# Mega_Shield-v13.net
KiCad netlist of a schematic drawn in EAGLE
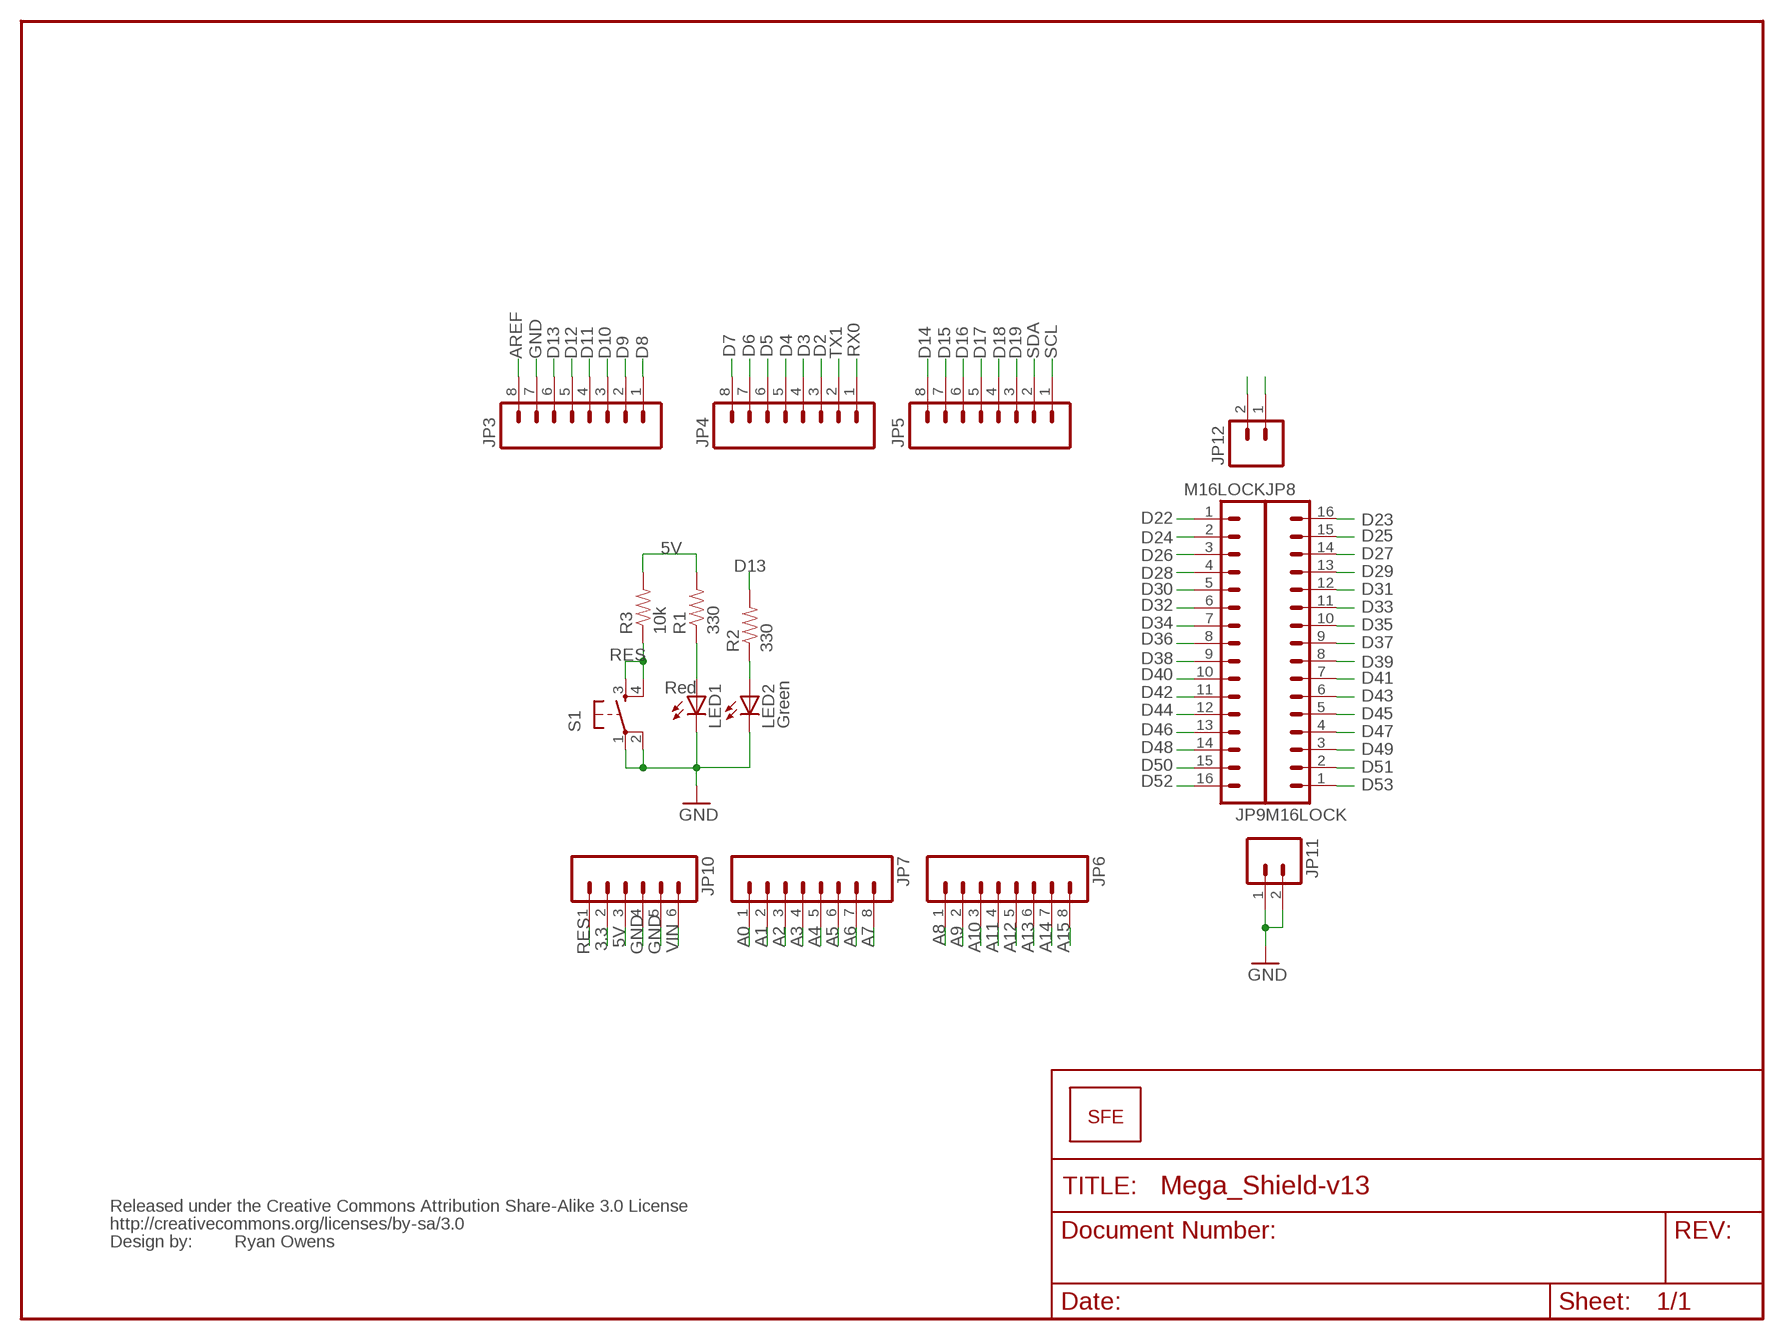
[diagram p0: schematic, sheet 1]

(export (version "E")
  (design (tool "Eeschema 10.0.6"))
  (components
    (comp (ref "JP3")
      (value "M08LOCK")
      (footprint "eagle-import:1X08_LOCK")
      (libsource (lib "eagle-import") (part "M08LOCK"))
    )
    (comp (ref "JP4")
      (value "M08LOCK")
      (footprint "eagle-import:1X08_LOCK")
      (libsource (lib "eagle-import") (part "M08LOCK"))
    )
    (comp (ref "JP5")
      (value "M08LOCK")
      (footprint "eagle-import:1X08_LOCK")
      (libsource (lib "eagle-import") (part "M08LOCK"))
    )
    (comp (ref "JP6")
      (value "M08LOCK")
      (footprint "eagle-import:1X08_LOCK")
      (libsource (lib "eagle-import") (part "M08LOCK"))
    )
    (comp (ref "JP7")
      (value "M08LOCK")
      (footprint "eagle-import:1X08_LOCK")
      (libsource (lib "eagle-import") (part "M08LOCK"))
    )
    (comp (ref "JP8")
      (value "M16LOCK")
      (footprint "eagle-import:1X16_LOCK")
      (libsource (lib "eagle-import") (part "M16LOCK"))
    )
    (comp (ref "JP9")
      (value "M16LOCK")
      (footprint "eagle-import:1X16_LOCK")
      (libsource (lib "eagle-import") (part "M16LOCK"))
    )
    (comp (ref "JP10")
      (value "M06LOCK")
      (footprint "eagle-import:1X06_LOCK")
      (libsource (lib "eagle-import") (part "M06LOCK"))
    )
    (comp (ref "JP11")
      (value "M02LOCK")
      (footprint "eagle-import:1X02_LOCK")
      (libsource (lib "eagle-import") (part "M02LOCK"))
    )
    (comp (ref "JP12")
      (value "M02LOCK")
      (footprint "eagle-import:1X02_LOCK")
      (libsource (lib "eagle-import") (part "M02LOCK"))
    )
    (comp (ref "LED1")
      (value "Red")
      (footprint "eagle-import:LED5MM")
      (libsource (lib "eagle-import") (part "LED5MM"))
    )
    (comp (ref "LED2")
      (value "Green")
      (footprint "eagle-import:LED5MM")
      (libsource (lib "eagle-import") (part "LED5MM"))
    )
    (comp (ref "R1")
      (value "330")
      (footprint "eagle-import:AXIAL-0.3")
      (libsource (lib "eagle-import") (part "RESISTORPTH1"))
    )
    (comp (ref "R2")
      (value "330")
      (footprint "eagle-import:AXIAL-0.3")
      (libsource (lib "eagle-import") (part "RESISTORPTH1"))
    )
    (comp (ref "R3")
      (value "10k")
      (footprint "eagle-import:AXIAL-0.3")
      (libsource (lib "eagle-import") (part "RESISTORPTH1"))
    )
    (comp (ref "S1")
      (value "TAC_SWITCHPTH")
      (footprint "eagle-import:TACTILE-PTH")
      (libsource (lib "eagle-import") (part "TAC_SWITCHPTH"))
    )
    (comp (ref "U$1")
      (value "LOGO-SFENEW")
      (footprint "eagle-import:SFE-NEW-WEBLOGO")
      (libsource (lib "eagle-import") (part "LOGO-SFENEW"))
    )
    (comp (ref "U$2")
      (value "CREATIVE_COMMONS")
      (footprint "eagle-import:CREATIVE_COMMONS")
      (libsource (lib "eagle-import") (part "CREATIVE_COMMONS"))
    )
  )
  (nets
    (net (code "1") (name "/3.3") (class "Default")
      (node (ref "JP10") (pin "2") (pinfunction "2_2") (pintype "passive"))
    )
    (net (code "2") (name "/5V") (class "Default")
      (node (ref "JP10") (pin "3") (pinfunction "3_3") (pintype "passive"))
      (node (ref "R1") (pin "P$2") (pinfunction "2_P$2") (pintype "passive"))
      (node (ref "R3") (pin "P$2") (pinfunction "2_P$2") (pintype "passive"))
    )
    (net (code "3") (name "/5V@1") (class "Default")
      (node (ref "JP12") (pin "1") (pinfunction "1_1") (pintype "passive"))
      (node (ref "JP12") (pin "2") (pinfunction "2_2") (pintype "passive"))
    )
    (net (code "4") (name "/A0") (class "Default")
      (node (ref "JP7") (pin "1") (pinfunction "1_1") (pintype "passive"))
    )
    (net (code "5") (name "/A1") (class "Default")
      (node (ref "JP7") (pin "2") (pinfunction "2_2") (pintype "passive"))
    )
    (net (code "6") (name "/A2") (class "Default")
      (node (ref "JP7") (pin "3") (pinfunction "3_3") (pintype "passive"))
    )
    (net (code "7") (name "/A3") (class "Default")
      (node (ref "JP7") (pin "4") (pinfunction "4_4") (pintype "passive"))
    )
    (net (code "8") (name "/A4") (class "Default")
      (node (ref "JP7") (pin "5") (pinfunction "5_5") (pintype "passive"))
    )
    (net (code "9") (name "/A5") (class "Default")
      (node (ref "JP7") (pin "6") (pinfunction "6_6") (pintype "passive"))
    )
    (net (code "10") (name "/A6") (class "Default")
      (node (ref "JP7") (pin "7") (pinfunction "7_7") (pintype "passive"))
    )
    (net (code "11") (name "/A7") (class "Default")
      (node (ref "JP7") (pin "8") (pinfunction "8_8") (pintype "passive"))
    )
    (net (code "12") (name "/A8") (class "Default")
      (node (ref "JP6") (pin "1") (pinfunction "1_1") (pintype "passive"))
    )
    (net (code "13") (name "/A9") (class "Default")
      (node (ref "JP6") (pin "2") (pinfunction "2_2") (pintype "passive"))
    )
    (net (code "14") (name "/A10") (class "Default")
      (node (ref "JP6") (pin "3") (pinfunction "3_3") (pintype "passive"))
    )
    (net (code "15") (name "/A11") (class "Default")
      (node (ref "JP6") (pin "4") (pinfunction "4_4") (pintype "passive"))
    )
    (net (code "16") (name "/A12") (class "Default")
      (node (ref "JP6") (pin "5") (pinfunction "5_5") (pintype "passive"))
    )
    (net (code "17") (name "/A13") (class "Default")
      (node (ref "JP6") (pin "6") (pinfunction "6_6") (pintype "passive"))
    )
    (net (code "18") (name "/A14") (class "Default")
      (node (ref "JP6") (pin "7") (pinfunction "7_7") (pintype "passive"))
    )
    (net (code "19") (name "/A15") (class "Default")
      (node (ref "JP6") (pin "8") (pinfunction "8_8") (pintype "passive"))
    )
    (net (code "20") (name "/AREF") (class "Default")
      (node (ref "JP3") (pin "8") (pinfunction "8_8") (pintype "passive"))
    )
    (net (code "21") (name "/D2") (class "Default")
      (node (ref "JP4") (pin "3") (pinfunction "3_3") (pintype "passive"))
    )
    (net (code "22") (name "/D3") (class "Default")
      (node (ref "JP4") (pin "4") (pinfunction "4_4") (pintype "passive"))
    )
    (net (code "23") (name "/D4") (class "Default")
      (node (ref "JP4") (pin "5") (pinfunction "5_5") (pintype "passive"))
    )
    (net (code "24") (name "/D5") (class "Default")
      (node (ref "JP4") (pin "6") (pinfunction "6_6") (pintype "passive"))
    )
    (net (code "25") (name "/D6") (class "Default")
      (node (ref "JP4") (pin "7") (pinfunction "7_7") (pintype "passive"))
    )
    (net (code "26") (name "/D7") (class "Default")
      (node (ref "JP4") (pin "8") (pinfunction "8_8") (pintype "passive"))
    )
    (net (code "27") (name "/D8") (class "Default")
      (node (ref "JP3") (pin "1") (pinfunction "1_1") (pintype "passive"))
    )
    (net (code "28") (name "/D9") (class "Default")
      (node (ref "JP3") (pin "2") (pinfunction "2_2") (pintype "passive"))
    )
    (net (code "29") (name "/D10") (class "Default")
      (node (ref "JP3") (pin "3") (pinfunction "3_3") (pintype "passive"))
    )
    (net (code "30") (name "/D11") (class "Default")
      (node (ref "JP3") (pin "4") (pinfunction "4_4") (pintype "passive"))
    )
    (net (code "31") (name "/D12") (class "Default")
      (node (ref "JP3") (pin "5") (pinfunction "5_5") (pintype "passive"))
    )
    (net (code "32") (name "/D13") (class "Default")
      (node (ref "JP3") (pin "6") (pinfunction "6_6") (pintype "passive"))
      (node (ref "R2") (pin "P$2") (pinfunction "2_P$2") (pintype "passive"))
    )
    (net (code "33") (name "/D14") (class "Default")
      (node (ref "JP5") (pin "8") (pinfunction "8_8") (pintype "passive"))
    )
    (net (code "34") (name "/D15") (class "Default")
      (node (ref "JP5") (pin "7") (pinfunction "7_7") (pintype "passive"))
    )
    (net (code "35") (name "/D16") (class "Default")
      (node (ref "JP5") (pin "6") (pinfunction "6_6") (pintype "passive"))
    )
    (net (code "36") (name "/D17") (class "Default")
      (node (ref "JP5") (pin "5") (pinfunction "5_5") (pintype "passive"))
    )
    (net (code "37") (name "/D18") (class "Default")
      (node (ref "JP5") (pin "4") (pinfunction "4_4") (pintype "passive"))
    )
    (net (code "38") (name "/D19") (class "Default")
      (node (ref "JP5") (pin "3") (pinfunction "3_3") (pintype "passive"))
    )
    (net (code "39") (name "/D22") (class "Default")
      (node (ref "JP9") (pin "1") (pinfunction "1_1") (pintype "passive"))
    )
    (net (code "40") (name "/D23") (class "Default")
      (node (ref "JP8") (pin "16") (pinfunction "16_16") (pintype "passive"))
    )
    (net (code "41") (name "/D24") (class "Default")
      (node (ref "JP9") (pin "2") (pinfunction "2_2") (pintype "passive"))
    )
    (net (code "42") (name "/D25") (class "Default")
      (node (ref "JP8") (pin "15") (pinfunction "15_15") (pintype "passive"))
    )
    (net (code "43") (name "/D26") (class "Default")
      (node (ref "JP9") (pin "3") (pinfunction "3_3") (pintype "passive"))
    )
    (net (code "44") (name "/D27") (class "Default")
      (node (ref "JP8") (pin "14") (pinfunction "14_14") (pintype "passive"))
    )
    (net (code "45") (name "/D28") (class "Default")
      (node (ref "JP9") (pin "4") (pinfunction "4_4") (pintype "passive"))
    )
    (net (code "46") (name "/D29") (class "Default")
      (node (ref "JP8") (pin "13") (pinfunction "13_13") (pintype "passive"))
    )
    (net (code "47") (name "/D30") (class "Default")
      (node (ref "JP9") (pin "5") (pinfunction "5_5") (pintype "passive"))
    )
    (net (code "48") (name "/D31") (class "Default")
      (node (ref "JP8") (pin "12") (pinfunction "12_12") (pintype "passive"))
    )
    (net (code "49") (name "/D32") (class "Default")
      (node (ref "JP9") (pin "6") (pinfunction "6_6") (pintype "passive"))
    )
    (net (code "50") (name "/D33") (class "Default")
      (node (ref "JP8") (pin "11") (pinfunction "11_11") (pintype "passive"))
    )
    (net (code "51") (name "/D34") (class "Default")
      (node (ref "JP9") (pin "7") (pinfunction "7_7") (pintype "passive"))
    )
    (net (code "52") (name "/D35") (class "Default")
      (node (ref "JP8") (pin "10") (pinfunction "10_10") (pintype "passive"))
    )
    (net (code "53") (name "/D36") (class "Default")
      (node (ref "JP9") (pin "8") (pinfunction "8_8") (pintype "passive"))
    )
    (net (code "54") (name "/D37") (class "Default")
      (node (ref "JP8") (pin "9") (pinfunction "9_9") (pintype "passive"))
    )
    (net (code "55") (name "/D38") (class "Default")
      (node (ref "JP9") (pin "9") (pinfunction "9_9") (pintype "passive"))
    )
    (net (code "56") (name "/D39") (class "Default")
      (node (ref "JP8") (pin "8") (pinfunction "8_8") (pintype "passive"))
    )
    (net (code "57") (name "/D40") (class "Default")
      (node (ref "JP9") (pin "10") (pinfunction "10_10") (pintype "passive"))
    )
    (net (code "58") (name "/D41") (class "Default")
      (node (ref "JP8") (pin "7") (pinfunction "7_7") (pintype "passive"))
    )
    (net (code "59") (name "/D42") (class "Default")
      (node (ref "JP9") (pin "11") (pinfunction "11_11") (pintype "passive"))
    )
    (net (code "60") (name "/D43") (class "Default")
      (node (ref "JP8") (pin "6") (pinfunction "6_6") (pintype "passive"))
    )
    (net (code "61") (name "/D44") (class "Default")
      (node (ref "JP9") (pin "12") (pinfunction "12_12") (pintype "passive"))
    )
    (net (code "62") (name "/D45") (class "Default")
      (node (ref "JP8") (pin "5") (pinfunction "5_5") (pintype "passive"))
    )
    (net (code "63") (name "/D46") (class "Default")
      (node (ref "JP9") (pin "13") (pinfunction "13_13") (pintype "passive"))
    )
    (net (code "64") (name "/D47") (class "Default")
      (node (ref "JP8") (pin "4") (pinfunction "4_4") (pintype "passive"))
    )
    (net (code "65") (name "/D48") (class "Default")
      (node (ref "JP9") (pin "14") (pinfunction "14_14") (pintype "passive"))
    )
    (net (code "66") (name "/D49") (class "Default")
      (node (ref "JP8") (pin "3") (pinfunction "3_3") (pintype "passive"))
    )
    (net (code "67") (name "/D50") (class "Default")
      (node (ref "JP9") (pin "15") (pinfunction "15_15") (pintype "passive"))
    )
    (net (code "68") (name "/D51") (class "Default")
      (node (ref "JP8") (pin "2") (pinfunction "2_2") (pintype "passive"))
    )
    (net (code "69") (name "/D52") (class "Default")
      (node (ref "JP9") (pin "16") (pinfunction "16_16") (pintype "passive"))
    )
    (net (code "70") (name "/D53") (class "Default")
      (node (ref "JP8") (pin "1") (pinfunction "1_1") (pintype "passive"))
    )
    (net (code "71") (name "/RES") (class "Default")
      (node (ref "JP10") (pin "1") (pinfunction "1_1") (pintype "passive"))
      (node (ref "R3") (pin "P$1") (pinfunction "1_P$1") (pintype "passive"))
      (node (ref "S1") (pin "3") (pinfunction "3_3") (pintype "passive"))
      (node (ref "S1") (pin "4") (pinfunction "4_4") (pintype "passive"))
    )
    (net (code "72") (name "/RX0") (class "Default")
      (node (ref "JP4") (pin "1") (pinfunction "1_1") (pintype "passive"))
    )
    (net (code "73") (name "/SCL") (class "Default")
      (node (ref "JP5") (pin "1") (pinfunction "1_1") (pintype "passive"))
    )
    (net (code "74") (name "/SDA") (class "Default")
      (node (ref "JP5") (pin "2") (pinfunction "2_2") (pintype "passive"))
    )
    (net (code "75") (name "/TX1") (class "Default")
      (node (ref "JP4") (pin "2") (pinfunction "2_2") (pintype "passive"))
    )
    (net (code "76") (name "/VIN") (class "Default")
      (node (ref "JP10") (pin "6") (pinfunction "6_6") (pintype "passive"))
    )
    (net (code "77") (name "GND") (class "Default")
      (node (ref "JP10") (pin "4") (pinfunction "4_4") (pintype "passive"))
      (node (ref "JP10") (pin "5") (pinfunction "5_5") (pintype "passive"))
      (node (ref "JP11") (pin "1") (pinfunction "1_1") (pintype "passive"))
      (node (ref "JP11") (pin "2") (pinfunction "2_2") (pintype "passive"))
      (node (ref "JP3") (pin "7") (pinfunction "7_7") (pintype "passive"))
      (node (ref "LED1") (pin "K") (pinfunction "C_K") (pintype "passive"))
      (node (ref "LED2") (pin "K") (pinfunction "C_K") (pintype "passive"))
      (node (ref "S1") (pin "1") (pinfunction "1_1") (pintype "passive"))
      (node (ref "S1") (pin "2") (pinfunction "2_2") (pintype "passive"))
    )
    (net (code "78") (name "Net-(R1-1)") (class "Default")
      (node (ref "LED1") (pin "A") (pinfunction "A_A") (pintype "passive"))
      (node (ref "R1") (pin "P$1") (pinfunction "1_P$1") (pintype "passive"))
    )
    (net (code "79") (name "Net-(R2-1)") (class "Default")
      (node (ref "LED2") (pin "A") (pinfunction "A_A") (pintype "passive"))
      (node (ref "R2") (pin "P$1") (pinfunction "1_P$1") (pintype "passive"))
    )
  )
)
